# Heaters.net
KiCad netlist of a schematic drawn in Altium Designer
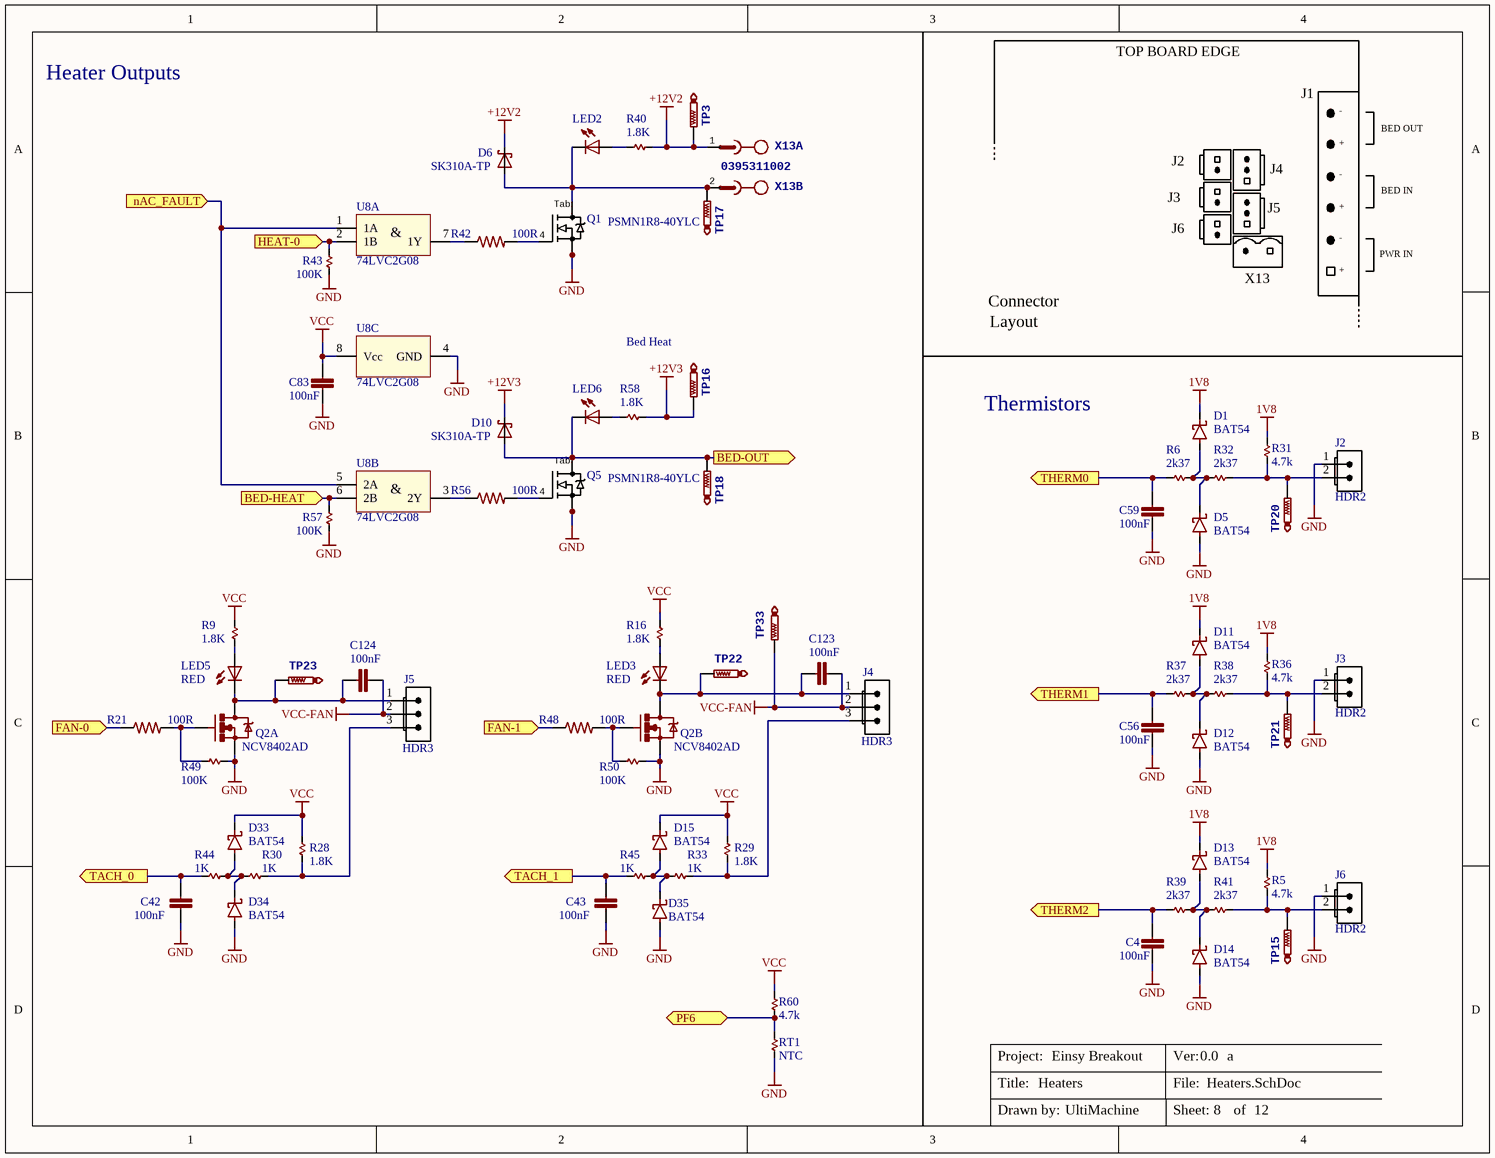
[diagram p0: Heaters.SchDoc]

(export (version "E")
  (design (tool "Eeschema 10.0.6"))
  (components
    (comp (ref "C4")
      (value "100nF")
      (footprint "C0402")
      (description "CAP CER 0402 100nF 16V 10% X7R")
      (fields (field (name "MANUFACTURER") "Murata") (field (name "TOLERANCE") "+/- 10%"))
      (libsource (lib "") (part "GRM155R71C104KA88D_1"))
    )
    (comp (ref "C42")
      (value "100nF")
      (footprint "C0402")
      (description "CAP CER 0402 100nF 16V 10% X7R")
      (fields (field (name "MANUFACTURER") "Murata") (field (name "TOLERANCE") "+/- 10%"))
      (libsource (lib "") (part "GRM155R71C104KA88D_1"))
    )
    (comp (ref "C43")
      (value "100nF")
      (footprint "C0402")
      (description "CAP CER 0402 100nF 16V 10% X7R")
      (fields (field (name "MANUFACTURER") "Murata") (field (name "TOLERANCE") "+/- 10%"))
      (libsource (lib "") (part "GRM155R71C104KA88D_1"))
    )
    (comp (ref "C56")
      (value "100nF")
      (footprint "C0402")
      (description "CAP CER 0402 100nF 16V 10% X7R")
      (fields (field (name "MANUFACTURER") "Murata") (field (name "TOLERANCE") "+/- 10%"))
      (libsource (lib "") (part "GRM155R71C104KA88D_1"))
    )
    (comp (ref "C59")
      (value "100nF")
      (footprint "C0402")
      (description "CAP CER 0402 100nF 16V 10% X7R")
      (fields (field (name "MANUFACTURER") "Murata") (field (name "TOLERANCE") "+/- 10%"))
      (libsource (lib "") (part "GRM155R71C104KA88D_1"))
    )
    (comp (ref "C83")
      (value "100nF")
      (footprint "C0402")
      (description "CAP CER 0402 100nF 16V 10% X7R")
      (fields (field (name "MANUFACTURER") "Murata") (field (name "TOLERANCE") "+/- 10%"))
      (libsource (lib "") (part "GRM155R71C104KA88D_1"))
    )
    (comp (ref "C123")
      (value "100nF")
      (footprint "C0402")
      (description "CAP CER 0402 100nF 16V 10% X7R")
      (fields (field (name "MANUFACTURER") "Murata") (field (name "TOLERANCE") "+/- 10%"))
      (libsource (lib "3Delight") (part "GRM155R71C104KA88D"))
    )
    (comp (ref "C124")
      (value "100nF")
      (footprint "C0402")
      (description "CAP CER 0402 100nF 16V 10% X7R")
      (fields (field (name "MANUFACTURER") "Murata") (field (name "TOLERANCE") "+/- 10%"))
      (libsource (lib "3Delight") (part "GRM155R71C104KA88D"))
    )
    (comp (ref "D1")
      (value "BAT54")
      (footprint "SOD523_IPC")
      (description "Diode Schottky 30V 100mA Surface Mount SOD-523")
      (fields (field (name "MANUFACTURER") "Diodes Incorporated") (field (name "TOLERANCE") "NA"))
      (libsource (lib "3Delight") (part "BAT54WT-7"))
    )
    (comp (ref "D5")
      (value "BAT54")
      (footprint "SOD523_IPC")
      (description "Diode Schottky 30V 100mA Surface Mount SOD-523")
      (fields (field (name "MANUFACTURER") "Diodes Incorporated") (field (name "TOLERANCE") "NA"))
      (libsource (lib "3Delight") (part "BAT54WT-7"))
    )
    (comp (ref "D6")
      (value "SK310A-TP")
      (footprint "SMA-SM")
      (description "DIODE Schottky 3A SMA")
      (fields (field (name "MANUFACTURER") "MCC") (field (name "PART") "SK310A"))
      (libsource (lib "3Delight") (part "SK310A"))
    )
    (comp (ref "D10")
      (value "SK310A-TP")
      (footprint "SMA-SM")
      (description "DIODE Schottky 3A SMA")
      (fields (field (name "MANUFACTURER") "MCC") (field (name "PART") "SK310A"))
      (libsource (lib "3Delight") (part "SK310A"))
    )
    (comp (ref "D11")
      (value "BAT54")
      (footprint "SOD523_IPC")
      (description "Diode Schottky 30V 100mA Surface Mount SOD-523")
      (fields (field (name "MANUFACTURER") "Diodes Incorporated") (field (name "TOLERANCE") "NA"))
      (libsource (lib "3Delight") (part "BAT54WT-7"))
    )
    (comp (ref "D12")
      (value "BAT54")
      (footprint "SOD523_IPC")
      (description "Diode Schottky 30V 100mA Surface Mount SOD-523")
      (fields (field (name "MANUFACTURER") "Diodes Incorporated") (field (name "TOLERANCE") "NA"))
      (libsource (lib "3Delight") (part "BAT54WT-7"))
    )
    (comp (ref "D13")
      (value "BAT54")
      (footprint "SOD523_IPC")
      (description "Diode Schottky 30V 100mA Surface Mount SOD-523")
      (fields (field (name "MANUFACTURER") "Diodes Incorporated") (field (name "TOLERANCE") "NA"))
      (libsource (lib "3Delight") (part "BAT54WT-7"))
    )
    (comp (ref "D14")
      (value "BAT54")
      (footprint "SOD523_IPC")
      (description "Diode Schottky 30V 100mA Surface Mount SOD-523")
      (fields (field (name "MANUFACTURER") "Diodes Incorporated") (field (name "TOLERANCE") "NA"))
      (libsource (lib "3Delight") (part "BAT54WT-7"))
    )
    (comp (ref "D15")
      (value "BAT54")
      (footprint "SOD523_IPC")
      (description "Diode Schottky 30V 100mA Surface Mount SOD-523")
      (fields (field (name "MANUFACTURER") "Diodes Incorporated") (field (name "TOLERANCE") "NA"))
      (libsource (lib "3Delight") (part "BAT54WT-7"))
    )
    (comp (ref "D33")
      (value "BAT54")
      (footprint "SOD523_IPC")
      (description "Diode Schottky 30V 100mA Surface Mount SOD-523")
      (fields (field (name "MANUFACTURER") "Diodes Incorporated") (field (name "TOLERANCE") "NA"))
      (libsource (lib "3Delight") (part "BAT54WT-7"))
    )
    (comp (ref "D34")
      (value "BAT54")
      (footprint "SOD523_IPC")
      (description "Diode Schottky 30V 100mA Surface Mount SOD-523")
      (fields (field (name "MANUFACTURER") "Diodes Incorporated") (field (name "TOLERANCE") "NA"))
      (libsource (lib "3Delight") (part "BAT54WT-7"))
    )
    (comp (ref "D35")
      (value "BAT54")
      (footprint "SOD523_IPC")
      (description "Diode Schottky 30V 100mA Surface Mount SOD-523")
      (fields (field (name "MANUFACTURER") "Diodes Incorporated") (field (name "TOLERANCE") "NA"))
      (libsource (lib "3Delight") (part "BAT54WT-7"))
    )
    (comp (ref "J2")
      (value "HDR2")
      (footprint "70543-02")
      (description "Connector 2pos")
      (fields (field (name "MANUFACTURER") "Molex") (field (name "PART") "10 Pin Conn"))
      (libsource (lib "Archim_0.4") (part "CONN 2PIN VERT 0.1{dblquote} SHRD LOCKING"))
    )
    (comp (ref "J3")
      (value "HDR2")
      (footprint "70543-02")
      (description "Connector 2pos")
      (fields (field (name "MANUFACTURER") "Molex") (field (name "PART") "10 Pin Conn"))
      (libsource (lib "Archim_0.4") (part "CONN 2PIN VERT 0.1{dblquote} SHRD LOCKING"))
    )
    (comp (ref "J4")
      (value "HDR3")
      (footprint "70543-03")
      (description "3 Positions Header, Shrouded Connector 0.100\" (2.54mm) Through Hole Gold")
      (fields (field (name "MANUFACTURER") "Molex") (field (name "PART") "3 Pin Conn VERT"))
      (libsource (lib "Archim_0.4") (part "CONN 3POS VERT 0.1{dblquote} SHRD LOCKING"))
    )
    (comp (ref "J5")
      (value "HDR3")
      (footprint "70543-03")
      (description "3 Positions Header, Shrouded Connector 0.100\" (2.54mm) Through Hole Gold")
      (fields (field (name "MANUFACTURER") "Molex") (field (name "PART") "3 Pin Conn VERT"))
      (libsource (lib "Archim_0.4") (part "CONN 3POS VERT 0.1{dblquote} SHRD LOCKING"))
    )
    (comp (ref "J6")
      (value "HDR2")
      (footprint "70543-02")
      (description "Connector 2pos")
      (fields (field (name "MANUFACTURER") "Molex") (field (name "PART") "10 Pin Conn"))
      (libsource (lib "Archim_0.4") (part "CONN 2PIN VERT 0.1{dblquote} SHRD LOCKING"))
    )
    (comp (ref "LED2")
      (value "RED")
      (footprint "LED2012120")
      (description "LED 0805 Red")
      (fields (field (name "MANUFACTURER") "Dialight") (field (name "TOLERANCE") "NA"))
      (libsource (lib "3Delight") (part "5988110107F"))
    )
    (comp (ref "LED3")
      (value "RED")
      (footprint "LED2012120")
      (description "LED 0805 Red")
      (fields
        (field (name "MANUFACTURER") "Dialight")
        (field (name "PART") "RED")
        (field (name "TOLERANCE") "NA")
      )
      (libsource (lib "3Delight") (part "5988110107F"))
    )
    (comp (ref "LED5")
      (value "RED")
      (footprint "LED2012120")
      (description "LED 0805 Red")
      (fields
        (field (name "MANUFACTURER") "Dialight")
        (field (name "PART") "RED")
        (field (name "TOLERANCE") "NA")
      )
      (libsource (lib "3Delight") (part "5988110107F"))
    )
    (comp (ref "LED6")
      (value "RED")
      (footprint "LED2012120")
      (description "LED 0805 Red")
      (fields (field (name "MANUFACTURER") "Dialight") (field (name "TOLERANCE") "NA"))
      (libsource (lib "3Delight") (part "5988110107F"))
    )
    (comp (ref "Q1")
      (value "PSMN1R8-40YLC")
      (footprint "SOT669")
      (description "MOSFET N-CH 40V 100A LFPAK")
      (fields (field (name "MANUFACTURER") "Nexperia") (field (name "TOLERANCE") "-NA-"))
      (libsource (lib "Transistors") (part "PSMN1R8-40YLC"))
    )
    (comp (ref "Q2")
      (value "NCV8402AD")
      (footprint "NCV8402AD-SOIC8")
      (description "IC DVR LOW SIDE 8-SOIC")
      (fields (field (name "MANUFACTURER") "On Semi") (field (name "PART") "NCV8402"))
      (libsource (lib "3Delight") (part "NCV8402AD"))
    )
    (comp (ref "Q5")
      (value "PSMN1R8-40YLC")
      (footprint "SOT669")
      (description "MOSFET N-CH 40V 100A LFPAK")
      (fields (field (name "MANUFACTURER") "Nexperia") (field (name "TOLERANCE") "-NA-"))
      (libsource (lib "Transistors") (part "PSMN1R8-40YLC"))
    )
    (comp (ref "R5")
      (value "4.7k")
      (footprint "R0402")
      (description "RES SMD 4.7K OHM 1% 1/16W 0402")
      (fields (field (name "MANUFACTURER") "Yageo") (field (name "TOLERANCE") "+/- 1%"))
      (libsource (lib "3Delight") (part "RC0402FR-074K7L"))
    )
    (comp (ref "R6")
      (value "2k37")
      (footprint "R0402")
      (description "RES SMD 2.37K OHM 1% 1/16W 0402")
      (fields (field (name "MANUFACTURER") "Yageo") (field (name "PART") "2.37k"))
      (libsource (lib "3Delight") (part "RC0402FR-072K37L"))
    )
    (comp (ref "R9")
      (value "1.8K")
      (footprint "R0402")
      (description "RES SMD 1.8K OHM 1% 1/16W 0402")
      (fields (field (name "MANUFACTURER") "Yageo") (field (name "PART") "1.8k"))
      (libsource (lib "3Delight") (part "RC0402FR-071K8L"))
    )
    (comp (ref "R16")
      (value "1.8K")
      (footprint "R0402")
      (description "RES SMD 1.8K OHM 1% 1/16W 0402")
      (fields (field (name "MANUFACTURER") "Yageo") (field (name "PART") "1.8k"))
      (libsource (lib "3Delight") (part "RC0402FR-071K8L"))
    )
    (comp (ref "R21")
      (value "100R")
      (footprint "R0402")
      (description "RES SMD 100 OHM 1% 1/16W 0402")
      (fields (field (name "MANUFACTURER") "Yageo") (field (name "PART") "100R 1% 0402"))
      (libsource (lib "Archim") (part "RES 100R 0402 1%"))
    )
    (comp (ref "R28")
      (value "1.8K")
      (footprint "R0402")
      (description "RES SMD 1.8K OHM 1% 1/16W 0402")
      (fields (field (name "MANUFACTURER") "Yageo") (field (name "PART") "1.8k"))
      (libsource (lib "3Delight") (part "RC0402FR-071K8L"))
    )
    (comp (ref "R29")
      (value "1.8K")
      (footprint "R0402")
      (description "RES SMD 1.8K OHM 1% 1/16W 0402")
      (fields (field (name "MANUFACTURER") "Yageo") (field (name "PART") "1.8k"))
      (libsource (lib "3Delight") (part "RC0402FR-071K8L"))
    )
    (comp (ref "R30")
      (value "1K")
      (footprint "R0402")
      (description "RES SMD 1K OHM 1% 1/16W 0402")
      (fields (field (name "MANUFACTURER") "Yageo") (field (name "PART") "1k"))
      (libsource (lib "3Delight") (part "RC0402FR-071KL"))
    )
    (comp (ref "R31")
      (value "4.7k")
      (footprint "R0402")
      (description "RES SMD 4.7K OHM 1% 1/16W 0402")
      (fields (field (name "MANUFACTURER") "Yageo") (field (name "TOLERANCE") "+/- 1%"))
      (libsource (lib "3Delight") (part "RC0402FR-074K7L"))
    )
    (comp (ref "R32")
      (value "2k37")
      (footprint "R0402")
      (description "RES SMD 2.37K OHM 1% 1/16W 0402")
      (fields (field (name "MANUFACTURER") "Yageo") (field (name "PART") "2.37k"))
      (libsource (lib "3Delight") (part "RC0402FR-072K37L"))
    )
    (comp (ref "R33")
      (value "1K")
      (footprint "R0402")
      (description "RES SMD 1K OHM 1% 1/16W 0402")
      (fields (field (name "MANUFACTURER") "Yageo") (field (name "PART") "1k"))
      (libsource (lib "3Delight") (part "RC0402FR-071KL"))
    )
    (comp (ref "R36")
      (value "4.7k")
      (footprint "R0402")
      (description "RES SMD 4.7K OHM 1% 1/16W 0402")
      (fields (field (name "MANUFACTURER") "Yageo") (field (name "TOLERANCE") "+/- 1%"))
      (libsource (lib "3Delight") (part "RC0402FR-074K7L"))
    )
    (comp (ref "R37")
      (value "2k37")
      (footprint "R0402")
      (description "RES SMD 2.37K OHM 1% 1/16W 0402")
      (fields (field (name "MANUFACTURER") "Yageo") (field (name "PART") "2.37k"))
      (libsource (lib "3Delight") (part "RC0402FR-072K37L"))
    )
    (comp (ref "R38")
      (value "2k37")
      (footprint "R0402")
      (description "RES SMD 2.37K OHM 1% 1/16W 0402")
      (fields (field (name "MANUFACTURER") "Yageo") (field (name "PART") "2.37k"))
      (libsource (lib "3Delight") (part "RC0402FR-072K37L"))
    )
    (comp (ref "R39")
      (value "2k37")
      (footprint "R0402")
      (description "RES SMD 2.37K OHM 1% 1/16W 0402")
      (fields (field (name "MANUFACTURER") "Yageo") (field (name "PART") "2.37k"))
      (libsource (lib "3Delight") (part "RC0402FR-072K37L"))
    )
    (comp (ref "R40")
      (value "1.8K")
      (footprint "R0402")
      (description "RES SMD 1.8K OHM 1% 1/16W 0402")
      (fields (field (name "MANUFACTURER") "Yageo") (field (name "PART") "1.8k"))
      (libsource (lib "3Delight") (part "RC0402FR-071K8L"))
    )
    (comp (ref "R41")
      (value "2k37")
      (footprint "R0402")
      (description "RES SMD 2.37K OHM 1% 1/16W 0402")
      (fields (field (name "MANUFACTURER") "Yageo") (field (name "PART") "2.37k"))
      (libsource (lib "3Delight") (part "RC0402FR-072K37L"))
    )
    (comp (ref "R42")
      (value "100R")
      (footprint "R0402")
      (description "RES SMD 100 OHM 1% 1/16W 0402")
      (fields (field (name "MANUFACTURER") "Yageo") (field (name "PART") "100R 1% 0402"))
      (libsource (lib "Archim") (part "RES 100R 0402 1%"))
    )
    (comp (ref "R43")
      (value "100K")
      (footprint "R0402")
      (description "RES 100K OHM 1% 1/16W 0402")
      (fields (field (name "MANUFACTURER") "Yageo") (field (name "TOLERANCE") "+/- 1%"))
      (libsource (lib "3Delight") (part "RC0402FR-07100KL"))
    )
    (comp (ref "R44")
      (value "1K")
      (footprint "R0402")
      (description "RES SMD 1K OHM 1% 1/16W 0402")
      (fields (field (name "MANUFACTURER") "Yageo") (field (name "PART") "1k"))
      (libsource (lib "3Delight") (part "RC0402FR-071KL"))
    )
    (comp (ref "R45")
      (value "1K")
      (footprint "R0402")
      (description "RES SMD 1K OHM 1% 1/16W 0402")
      (fields (field (name "MANUFACTURER") "Yageo") (field (name "PART") "1k"))
      (libsource (lib "3Delight") (part "RC0402FR-071KL"))
    )
    (comp (ref "R48")
      (value "100R")
      (footprint "R0402")
      (description "RES SMD 100 OHM 1% 1/16W 0402")
      (fields (field (name "MANUFACTURER") "Yageo") (field (name "PART") "100R 1% 0402"))
      (libsource (lib "Archim") (part "RES 100R 0402 1%"))
    )
    (comp (ref "R49")
      (value "100K")
      (footprint "R0402")
      (description "RES 100K OHM 1% 1/16W 0402")
      (fields (field (name "MANUFACTURER") "Yageo") (field (name "TOLERANCE") "+/- 1%"))
      (libsource (lib "3Delight") (part "RC0402FR-07100KL"))
    )
    (comp (ref "R50")
      (value "100K")
      (footprint "R0402")
      (description "RES 100K OHM 1% 1/16W 0402")
      (fields (field (name "MANUFACTURER") "Yageo") (field (name "TOLERANCE") "+/- 1%"))
      (libsource (lib "3Delight") (part "RC0402FR-07100KL"))
    )
    (comp (ref "R56")
      (value "100R")
      (footprint "R0402")
      (description "RES SMD 100 OHM 1% 1/16W 0402")
      (fields (field (name "MANUFACTURER") "Yageo") (field (name "PART") "100R 1% 0402"))
      (libsource (lib "Archim") (part "RES 100R 0402 1%"))
    )
    (comp (ref "R57")
      (value "100K")
      (footprint "R0402")
      (description "RES 100K OHM 1% 1/16W 0402")
      (fields (field (name "MANUFACTURER") "Yageo") (field (name "TOLERANCE") "+/- 1%"))
      (libsource (lib "3Delight") (part "RC0402FR-07100KL"))
    )
    (comp (ref "R58")
      (value "1.8K")
      (footprint "R0402")
      (description "RES SMD 1.8K OHM 1% 1/16W 0402")
      (fields (field (name "MANUFACTURER") "Yageo") (field (name "PART") "1.8k"))
      (libsource (lib "3Delight") (part "RC0402FR-071K8L"))
    )
    (comp (ref "R60")
      (value "4.7k")
      (footprint "R0402")
      (description "RES SMD 4.7K OHM 1% 1/16W 0402")
      (fields (field (name "MANUFACTURER") "Yageo") (field (name "TOLERANCE") "+/- 1%"))
      (libsource (lib "3Delight") (part "RC0402FR-074K7L"))
    )
    (comp (ref "RT1")
      (value "NTC")
      (footprint "R0402")
      (description "NTC THERMISTOR 100K OHM 5% 0402")
      (fields (field (name "MANUFACTURER") "TDK") (field (name "TOLERANCE") "5%"))
      (libsource (lib "Resistors") (part "THERM_NTC"))
    )
    (comp (ref "TP3")
      (value "TestPoint")
      (footprint "TP1-27")
      (description "Test Point")
      (libsource (lib "") (part "TestPoint_1"))
    )
    (comp (ref "TP15")
      (value "TestPoint")
      (footprint "TP1-27")
      (description "Test Point")
      (libsource (lib "3Delight") (part "TestPoint"))
    )
    (comp (ref "TP16")
      (value "TestPoint")
      (footprint "TP1-27")
      (description "Test Point")
      (libsource (lib "") (part "TestPoint_1"))
    )
    (comp (ref "TP17")
      (value "TestPoint")
      (footprint "TP1-27")
      (description "Test Point")
      (libsource (lib "3Delight") (part "TestPoint"))
    )
    (comp (ref "TP18")
      (value "TestPoint")
      (footprint "TP1-27")
      (description "Test Point")
      (libsource (lib "3Delight") (part "TestPoint"))
    )
    (comp (ref "TP20")
      (value "TestPoint")
      (footprint "TP1-27")
      (description "Test Point")
      (libsource (lib "3Delight") (part "TestPoint"))
    )
    (comp (ref "TP21")
      (value "TestPoint")
      (footprint "TP1-27")
      (description "Test Point")
      (libsource (lib "3Delight") (part "TestPoint"))
    )
    (comp (ref "TP22")
      (value "TestPoint")
      (footprint "TP1-27")
      (description "Test Point")
      (libsource (lib "") (part "TestPoint_2"))
    )
    (comp (ref "TP23")
      (value "TestPoint")
      (footprint "TP1-27")
      (description "Test Point")
      (libsource (lib "") (part "TestPoint_2"))
    )
    (comp (ref "TP33")
      (value "TestPoint")
      (footprint "TP1-27")
      (description "Test Point")
      (libsource (lib "") (part "TestPoint_1"))
    )
    (comp (ref "U8")
      (value "74LVC2G08")
      (footprint "VSSOP8")
      (description "IC GATE AND 2CH 2-INP 8-VSSOP")
      (fields (field (name "TOLERANCE") "-NA-") (field (name "MANUFACTURER") "Nexperia"))
      (libsource (lib "ICs-Logic") (part "74LVC2G08"))
    )
    (comp (ref "X13")
      (value "0395311002")
      (footprint "MSTBV2")
      (description "Conn - 5.08mm Pitch Fixed")
      (fields (field (name "MANUFACTURER") "Molex") (field (name "PART") "2POS"))
      (libsource (lib "3Delight") (part "0395311002"))
    )
  )
  (nets
    (net (code "1") (name "+12V2") (class "Default")
      (node (ref "D6") (pin "C") (pinfunction "C_C") (pintype "passive"))
      (node (ref "R40") (pin "1") (pinfunction "1_1") (pintype "passive"))
      (node (ref "TP3") (pin "TP") (pinfunction "TP_TP") (pintype "passive"))
      (node (ref "X13") (pin "1") (pinfunction "1_1") (pintype "passive"))
    )
    (net (code "2") (name "+12V3") (class "Default")
      (node (ref "D10") (pin "C") (pinfunction "C_C") (pintype "passive"))
      (node (ref "R58") (pin "1") (pinfunction "1_1") (pintype "passive"))
      (node (ref "TP16") (pin "TP") (pinfunction "TP_TP") (pintype "passive"))
    )
    (net (code "3") (name "/BED-HEAT") (class "Default")
      (node (ref "R57") (pin "2") (pinfunction "2_2") (pintype "passive"))
      (node (ref "U8") (pin "6") (pinfunction "2B_6") (pintype "passive"))
    )
    (net (code "4") (name "/BED-OUT") (class "Default")
      (node (ref "D10") (pin "A") (pinfunction "A_A") (pintype "passive"))
      (node (ref "LED6") (pin "C") (pinfunction "C_C") (pintype "passive"))
      (node (ref "Q5") (pin "MB") (pinfunction "D_MB") (pintype "passive"))
      (node (ref "TP18") (pin "TP") (pinfunction "TP_TP") (pintype "passive"))
    )
    (net (code "5") (name "/FAN-0") (class "Default")
      (node (ref "R21") (pin "1") (pinfunction "1_1") (pintype "passive"))
    )
    (net (code "6") (name "/FAN-1") (class "Default")
      (node (ref "R48") (pin "1") (pinfunction "1_1") (pintype "passive"))
    )
    (net (code "7") (name "/HEAT-0") (class "Default")
      (node (ref "R43") (pin "2") (pinfunction "2_2") (pintype "passive"))
      (node (ref "U8") (pin "2") (pinfunction "1B_2") (pintype "passive"))
    )
    (net (code "8") (name "/PF6") (class "Default")
      (node (ref "R60") (pin "1") (pinfunction "1_1") (pintype "passive"))
      (node (ref "RT1") (pin "2") (pinfunction "2_2") (pintype "passive"))
    )
    (net (code "9") (name "/TACH_0") (class "Default")
      (node (ref "C42") (pin "1") (pinfunction "1_1") (pintype "passive"))
      (node (ref "R44") (pin "1") (pinfunction "1_1") (pintype "passive"))
    )
    (net (code "10") (name "/TACH_1") (class "Default")
      (node (ref "C43") (pin "1") (pinfunction "1_1") (pintype "passive"))
      (node (ref "R45") (pin "1") (pinfunction "1_1") (pintype "passive"))
    )
    (net (code "11") (name "/THERM0") (class "Default")
      (node (ref "C59") (pin "1") (pinfunction "1_1") (pintype "passive"))
      (node (ref "R6") (pin "2") (pinfunction "2_2") (pintype "passive"))
    )
    (net (code "12") (name "/THERM1") (class "Default")
      (node (ref "C56") (pin "1") (pinfunction "1_1") (pintype "passive"))
      (node (ref "R37") (pin "2") (pinfunction "2_2") (pintype "passive"))
    )
    (net (code "13") (name "/THERM2") (class "Default")
      (node (ref "C4") (pin "1") (pinfunction "1_1") (pintype "passive"))
      (node (ref "R39") (pin "2") (pinfunction "2_2") (pintype "passive"))
    )
    (net (code "14") (name "/nAC_FAULT") (class "Default")
      (node (ref "U8") (pin "1") (pinfunction "1A_1") (pintype "passive"))
      (node (ref "U8") (pin "5") (pinfunction "2A_5") (pintype "passive"))
    )
    (net (code "15") (name "1V8") (class "Default")
      (node (ref "D1") (pin "K") (pinfunction "K_K") (pintype "passive"))
      (node (ref "D11") (pin "K") (pinfunction "K_K") (pintype "passive"))
      (node (ref "D13") (pin "K") (pinfunction "K_K") (pintype "passive"))
      (node (ref "R31") (pin "2") (pinfunction "2_2") (pintype "passive"))
      (node (ref "R36") (pin "2") (pinfunction "2_2") (pintype "passive"))
      (node (ref "R5") (pin "2") (pinfunction "2_2") (pintype "passive"))
    )
    (net (code "16") (name "GND") (class "Default")
      (node (ref "C4") (pin "2") (pinfunction "2_2") (pintype "passive"))
      (node (ref "C42") (pin "2") (pinfunction "2_2") (pintype "passive"))
      (node (ref "C43") (pin "2") (pinfunction "2_2") (pintype "passive"))
      (node (ref "C56") (pin "2") (pinfunction "2_2") (pintype "passive"))
      (node (ref "C59") (pin "2") (pinfunction "2_2") (pintype "passive"))
      (node (ref "C83") (pin "2") (pinfunction "2_2") (pintype "passive"))
      (node (ref "D12") (pin "A") (pinfunction "A_A") (pintype "passive"))
      (node (ref "D14") (pin "A") (pinfunction "A_A") (pintype "passive"))
      (node (ref "D34") (pin "A") (pinfunction "A_A") (pintype "passive"))
      (node (ref "D35") (pin "A") (pinfunction "A_A") (pintype "passive"))
      (node (ref "D5") (pin "A") (pinfunction "A_A") (pintype "passive"))
      (node (ref "J2") (pin "1") (pinfunction "S_1") (pintype "passive"))
      (node (ref "J3") (pin "1") (pinfunction "S_1") (pintype "passive"))
      (node (ref "J6") (pin "1") (pinfunction "S_1") (pintype "passive"))
      (node (ref "Q1") (pin "1") (pinfunction "S_1") (pintype "passive"))
      (node (ref "Q1") (pin "2") (pinfunction "S_2") (pintype "passive"))
      (node (ref "Q1") (pin "3") (pinfunction "S_3") (pintype "passive"))
      (node (ref "Q2") (pin "1") (pinfunction "S_1") (pintype "passive"))
      (node (ref "Q2") (pin "3") (pinfunction "S_3") (pintype "passive"))
      (node (ref "Q5") (pin "1") (pinfunction "S_1") (pintype "passive"))
      (node (ref "Q5") (pin "2") (pinfunction "S_2") (pintype "passive"))
      (node (ref "Q5") (pin "3") (pinfunction "S_3") (pintype "passive"))
      (node (ref "R43") (pin "1") (pinfunction "1_1") (pintype "passive"))
      (node (ref "R49") (pin "2") (pinfunction "2_2") (pintype "passive"))
      (node (ref "R50") (pin "2") (pinfunction "2_2") (pintype "passive"))
      (node (ref "R57") (pin "1") (pinfunction "1_1") (pintype "passive"))
      (node (ref "RT1") (pin "1") (pinfunction "1_1") (pintype "passive"))
      (node (ref "U8") (pin "4") (pinfunction "GND_4") (pintype "passive"))
    )
    (net (code "17") (name "Net-(D1-PadA)") (class "Default")
      (node (ref "D1") (pin "A") (pinfunction "A_A") (pintype "passive"))
      (node (ref "D5") (pin "K") (pinfunction "K_K") (pintype "passive"))
      (node (ref "R32") (pin "2") (pinfunction "2_2") (pintype "passive"))
      (node (ref "R6") (pin "1") (pinfunction "1_1") (pintype "passive"))
    )
    (net (code "18") (name "Net-(D11-PadA)") (class "Default")
      (node (ref "D11") (pin "A") (pinfunction "A_A") (pintype "passive"))
      (node (ref "D12") (pin "K") (pinfunction "K_K") (pintype "passive"))
      (node (ref "R37") (pin "1") (pinfunction "1_1") (pintype "passive"))
      (node (ref "R38") (pin "2") (pinfunction "2_2") (pintype "passive"))
    )
    (net (code "19") (name "Net-(D13-PadA)") (class "Default")
      (node (ref "D13") (pin "A") (pinfunction "A_A") (pintype "passive"))
      (node (ref "D14") (pin "K") (pinfunction "K_K") (pintype "passive"))
      (node (ref "R39") (pin "1") (pinfunction "1_1") (pintype "passive"))
      (node (ref "R41") (pin "2") (pinfunction "2_2") (pintype "passive"))
    )
    (net (code "20") (name "Net-(D15-PadA)") (class "Default")
      (node (ref "D15") (pin "A") (pinfunction "A_A") (pintype "passive"))
      (node (ref "D35") (pin "K") (pinfunction "K_K") (pintype "passive"))
      (node (ref "R33") (pin "1") (pinfunction "1_1") (pintype "passive"))
      (node (ref "R45") (pin "2") (pinfunction "2_2") (pintype "passive"))
    )
    (net (code "21") (name "Net-(D33-PadA)") (class "Default")
      (node (ref "D33") (pin "A") (pinfunction "A_A") (pintype "passive"))
      (node (ref "D34") (pin "K") (pinfunction "K_K") (pintype "passive"))
      (node (ref "R30") (pin "1") (pinfunction "1_1") (pintype "passive"))
      (node (ref "R44") (pin "2") (pinfunction "2_2") (pintype "passive"))
    )
    (net (code "22") (name "Net-(J2-S-Pad2)") (class "Default")
      (node (ref "J2") (pin "2") (pinfunction "S_2") (pintype "passive"))
      (node (ref "R31") (pin "1") (pinfunction "1_1") (pintype "passive"))
      (node (ref "R32") (pin "1") (pinfunction "1_1") (pintype "passive"))
      (node (ref "TP20") (pin "TP") (pinfunction "TP_TP") (pintype "passive"))
    )
    (net (code "23") (name "Net-(J3-S-Pad2)") (class "Default")
      (node (ref "J3") (pin "2") (pinfunction "S_2") (pintype "passive"))
      (node (ref "R36") (pin "1") (pinfunction "1_1") (pintype "passive"))
      (node (ref "R38") (pin "1") (pinfunction "1_1") (pintype "passive"))
      (node (ref "TP21") (pin "TP") (pinfunction "TP_TP") (pintype "passive"))
    )
    (net (code "24") (name "Net-(J4-S-Pad3)") (class "Default")
      (node (ref "J4") (pin "3") (pinfunction "S_3") (pintype "passive"))
      (node (ref "R29") (pin "1") (pinfunction "1_1") (pintype "passive"))
      (node (ref "R33") (pin "2") (pinfunction "2_2") (pintype "passive"))
    )
    (net (code "25") (name "Net-(J5-S-Pad3)") (class "Default")
      (node (ref "J5") (pin "3") (pinfunction "S_3") (pintype "passive"))
      (node (ref "R28") (pin "1") (pinfunction "1_1") (pintype "passive"))
      (node (ref "R30") (pin "2") (pinfunction "2_2") (pintype "passive"))
    )
    (net (code "26") (name "Net-(J6-S-Pad2)") (class "Default")
      (node (ref "J6") (pin "2") (pinfunction "S_2") (pintype "passive"))
      (node (ref "R41") (pin "1") (pinfunction "1_1") (pintype "passive"))
      (node (ref "R5") (pin "1") (pinfunction "1_1") (pintype "passive"))
      (node (ref "TP15") (pin "TP") (pinfunction "TP_TP") (pintype "passive"))
    )
    (net (code "27") (name "Net-(LED2-PadA)") (class "Default")
      (node (ref "LED2") (pin "A") (pinfunction "A_A") (pintype "passive"))
      (node (ref "R40") (pin "2") (pinfunction "2_2") (pintype "passive"))
    )
    (net (code "28") (name "Net-(LED3-PadA)") (class "Default")
      (node (ref "LED3") (pin "A") (pinfunction "A_A") (pintype "passive"))
      (node (ref "R16") (pin "2") (pinfunction "2_2") (pintype "passive"))
    )
    (net (code "29") (name "Net-(LED5-PadA)") (class "Default")
      (node (ref "LED5") (pin "A") (pinfunction "A_A") (pintype "passive"))
      (node (ref "R9") (pin "2") (pinfunction "2_2") (pintype "passive"))
    )
    (net (code "30") (name "Net-(LED6-PadA)") (class "Default")
      (node (ref "LED6") (pin "A") (pinfunction "A_A") (pintype "passive"))
      (node (ref "R58") (pin "2") (pinfunction "2_2") (pintype "passive"))
    )
    (net (code "31") (name "Net-(Q1-D)") (class "Default")
      (node (ref "D6") (pin "A") (pinfunction "A_A") (pintype "passive"))
      (node (ref "LED2") (pin "C") (pinfunction "C_C") (pintype "passive"))
      (node (ref "Q1") (pin "MB") (pinfunction "D_MB") (pintype "passive"))
      (node (ref "TP17") (pin "TP") (pinfunction "TP_TP") (pintype "passive"))
      (node (ref "X13") (pin "2") (pinfunction "1_2") (pintype "passive"))
    )
    (net (code "32") (name "Net-(Q1-G)") (class "Default")
      (node (ref "Q1") (pin "4") (pinfunction "G_4") (pintype "passive"))
      (node (ref "R42") (pin "2") (pinfunction "2_2") (pintype "passive"))
    )
    (net (code "33") (name "Net-(Q2A-D)") (class "Default")
      (node (ref "C124") (pin "1") (pinfunction "1_1") (pintype "passive"))
      (node (ref "J5") (pin "1") (pinfunction "S_1") (pintype "passive"))
      (node (ref "LED5") (pin "C") (pinfunction "C_C") (pintype "passive"))
      (node (ref "Q2") (pin "7") (pinfunction "D_7") (pintype "passive"))
      (node (ref "TP23") (pin "TP") (pinfunction "TP_TP") (pintype "passive"))
    )
    (net (code "34") (name "Net-(Q2A-G)") (class "Default")
      (node (ref "Q2") (pin "2") (pinfunction "G_2") (pintype "passive"))
      (node (ref "R21") (pin "2") (pinfunction "2_2") (pintype "passive"))
      (node (ref "R49") (pin "1") (pinfunction "1_1") (pintype "passive"))
    )
    (net (code "35") (name "Net-(Q2B-D)") (class "Default")
      (node (ref "C123") (pin "1") (pinfunction "1_1") (pintype "passive"))
      (node (ref "J4") (pin "1") (pinfunction "S_1") (pintype "passive"))
      (node (ref "LED3") (pin "C") (pinfunction "C_C") (pintype "passive"))
      (node (ref "Q2") (pin "5") (pinfunction "D_5") (pintype "passive"))
      (node (ref "TP22") (pin "TP") (pinfunction "TP_TP") (pintype "passive"))
    )
    (net (code "36") (name "Net-(Q2B-G)") (class "Default")
      (node (ref "Q2") (pin "4") (pinfunction "G_4") (pintype "passive"))
      (node (ref "R48") (pin "2") (pinfunction "2_2") (pintype "passive"))
      (node (ref "R50") (pin "1") (pinfunction "1_1") (pintype "passive"))
    )
    (net (code "37") (name "Net-(Q5-G)") (class "Default")
      (node (ref "Q5") (pin "4") (pinfunction "G_4") (pintype "passive"))
      (node (ref "R56") (pin "2") (pinfunction "2_2") (pintype "passive"))
    )
    (net (code "38") (name "Net-(U8A-1Y)") (class "Default")
      (node (ref "R42") (pin "1") (pinfunction "1_1") (pintype "passive"))
      (node (ref "U8") (pin "7") (pinfunction "1Y_7") (pintype "passive"))
    )
    (net (code "39") (name "Net-(U8B-2Y)") (class "Default")
      (node (ref "R56") (pin "1") (pinfunction "1_1") (pintype "passive"))
      (node (ref "U8") (pin "3") (pinfunction "2Y_3") (pintype "passive"))
    )
    (net (code "40") (name "VCC") (class "Default")
      (node (ref "C83") (pin "1") (pinfunction "1_1") (pintype "passive"))
      (node (ref "D15") (pin "K") (pinfunction "K_K") (pintype "passive"))
      (node (ref "D33") (pin "K") (pinfunction "K_K") (pintype "passive"))
      (node (ref "R16") (pin "1") (pinfunction "1_1") (pintype "passive"))
      (node (ref "R28") (pin "2") (pinfunction "2_2") (pintype "passive"))
      (node (ref "R29") (pin "2") (pinfunction "2_2") (pintype "passive"))
      (node (ref "R60") (pin "2") (pinfunction "2_2") (pintype "passive"))
      (node (ref "R9") (pin "1") (pinfunction "1_1") (pintype "passive"))
      (node (ref "U8") (pin "8") (pinfunction "Vcc_8") (pintype "passive"))
    )
    (net (code "41") (name "VCC-FAN") (class "Default")
      (node (ref "C123") (pin "2") (pinfunction "2_2") (pintype "passive"))
      (node (ref "C124") (pin "2") (pinfunction "2_2") (pintype "passive"))
      (node (ref "J4") (pin "2") (pinfunction "S_2") (pintype "passive"))
      (node (ref "J5") (pin "2") (pinfunction "S_2") (pintype "passive"))
      (node (ref "TP33") (pin "TP") (pinfunction "TP_TP") (pintype "passive"))
    )
    (net (code "42") (name "unconnected-(U8A-NC-Pad23)") (class "Default")
      (node (ref "U8") (pin "23") (pinfunction "NC_23") (pintype "passive"))
    )
  )
)
